# SV60mALEDs.net
KiCad netlist of a schematic drawn in EAGLE
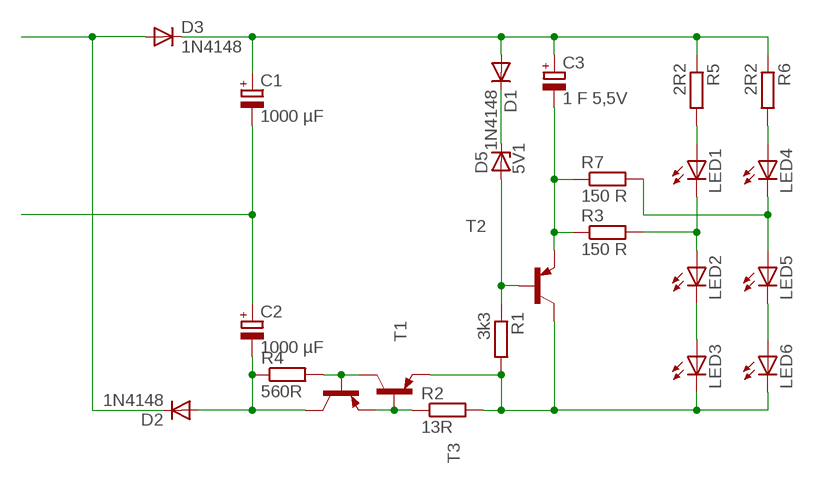
[diagram p0: schematic, sheet 1]

(export (version "E")
  (design (tool "Eeschema 10.0.6"))
  (components
    (comp (ref "C1")
      (value "1000 µF")
      (footprint "eagle-import:E5-10,5")
      (libsource (lib "eagle-import") (part "CPOL-EUE5-10.5"))
    )
    (comp (ref "C2")
      (value "1000 µF")
      (footprint "eagle-import:E5-10,5")
      (libsource (lib "eagle-import") (part "CPOL-EUE5-10.5"))
    )
    (comp (ref "C3")
      (value "1 F 5,5V")
      (footprint "eagle-import:E3,5-10")
      (libsource (lib "eagle-import") (part "CPOL-EUE3.5-10"))
    )
    (comp (ref "D1")
      (value "1N4148")
      (footprint "eagle-import:DO35-10")
      (libsource (lib "eagle-import") (part "1N4148DO35-10"))
    )
    (comp (ref "D2")
      (value "1N4148")
      (footprint "eagle-import:DO35-10")
      (libsource (lib "eagle-import") (part "1N4148DO35-10"))
    )
    (comp (ref "D3")
      (value "1N4148")
      (footprint "eagle-import:DO35-10")
      (libsource (lib "eagle-import") (part "1N4148DO35-10"))
    )
    (comp (ref "D5")
      (value "5V1")
      (footprint "eagle-import:SOD81")
      (libsource (lib "eagle-import") (part "BZD23"))
    )
    (comp (ref "LED1")
      (value "LED5MM")
      (footprint "eagle-import:LED5MM")
      (libsource (lib "eagle-import") (part "LED5MM"))
    )
    (comp (ref "LED2")
      (value "LED5MM")
      (footprint "eagle-import:LED5MM")
      (libsource (lib "eagle-import") (part "LED5MM"))
    )
    (comp (ref "LED3")
      (value "LED5MM")
      (footprint "eagle-import:LED5MM")
      (libsource (lib "eagle-import") (part "LED5MM"))
    )
    (comp (ref "LED4")
      (value "LED5MM")
      (footprint "eagle-import:LED5MM")
      (libsource (lib "eagle-import") (part "LED5MM"))
    )
    (comp (ref "LED5")
      (value "LED5MM")
      (footprint "eagle-import:LED5MM")
      (libsource (lib "eagle-import") (part "LED5MM"))
    )
    (comp (ref "LED6")
      (value "LED5MM")
      (footprint "eagle-import:LED5MM")
      (libsource (lib "eagle-import") (part "LED5MM"))
    )
    (comp (ref "R1")
      (value "3k3")
      (footprint "eagle-import:0207_10")
      (libsource (lib "eagle-import") (part "R-EU_0207/10"))
    )
    (comp (ref "R2")
      (value "13R")
      (footprint "eagle-import:0207_10")
      (libsource (lib "eagle-import") (part "R-EU_0207/10"))
    )
    (comp (ref "R3")
      (value "150 R")
      (footprint "eagle-import:0207_10")
      (libsource (lib "eagle-import") (part "R-EU_0207/10"))
    )
    (comp (ref "R4")
      (value "560R")
      (footprint "eagle-import:0207_12")
      (libsource (lib "eagle-import") (part "R-EU_0207/12"))
    )
    (comp (ref "R5")
      (value "2R2")
      (footprint "eagle-import:0207_10")
      (libsource (lib "eagle-import") (part "R-EU_0207/10"))
    )
    (comp (ref "R6")
      (value "2R2")
      (footprint "eagle-import:0207_10")
      (libsource (lib "eagle-import") (part "R-EU_0207/10"))
    )
    (comp (ref "R7")
      (value "150 R")
      (footprint "eagle-import:0207_10")
      (libsource (lib "eagle-import") (part "R-EU_0207/10"))
    )
    (comp (ref "T1")
      (value "2N2907-PNP-TO18-EBC")
      (footprint "eagle-import:TO18")
      (libsource (lib "eagle-import") (part "-PNP-TO18-EBC2N2907"))
    )
    (comp (ref "T2")
      (value "2N2907-PNP-TO18-EBC")
      (footprint "eagle-import:TO18")
      (libsource (lib "eagle-import") (part "-PNP-TO18-EBC2N2907"))
    )
    (comp (ref "T3")
      (value "2N2907-PNP-TO18-EBC")
      (footprint "eagle-import:TO18")
      (libsource (lib "eagle-import") (part "-PNP-TO18-EBC2N2907"))
    )
  )
  (nets
    (net (code "1") (name "Net-(C1-Pad+)") (class "Default")
      (node (ref "C1") (pin "+") (pinfunction "+_+") (pintype "passive"))
      (node (ref "C3") (pin "+") (pinfunction "+_+") (pintype "passive"))
      (node (ref "D1") (pin "A") (pinfunction "A_A") (pintype "passive"))
      (node (ref "D3") (pin "C") (pinfunction "C_C") (pintype "passive"))
      (node (ref "R5") (pin "1") (pinfunction "1_1") (pintype "passive"))
      (node (ref "R6") (pin "1") (pinfunction "1_1") (pintype "passive"))
    )
    (net (code "2") (name "Net-(C1-Pad-)") (class "Default")
      (node (ref "C1") (pin "-") (pinfunction "-_-") (pintype "passive"))
      (node (ref "C2") (pin "+") (pinfunction "+_+") (pintype "passive"))
    )
    (net (code "3") (name "Net-(D1-PadC)") (class "Default")
      (node (ref "D1") (pin "C") (pinfunction "C_C") (pintype "passive"))
      (node (ref "D5") (pin "C") (pinfunction "C_C") (pintype "passive"))
    )
    (net (code "4") (name "Net-(D2-PadC)") (class "Default")
      (node (ref "D2") (pin "C") (pinfunction "C_C") (pintype "passive"))
      (node (ref "D3") (pin "A") (pinfunction "A_A") (pintype "passive"))
    )
    (net (code "5") (name "Net-(LED1-C)") (class "Default")
      (node (ref "LED1") (pin "K") (pinfunction "C_K") (pintype "passive"))
      (node (ref "LED2") (pin "A") (pinfunction "A_A") (pintype "passive"))
      (node (ref "R3") (pin "2") (pinfunction "2_2") (pintype "passive"))
    )
    (net (code "6") (name "Net-(LED1-PadA)") (class "Default")
      (node (ref "LED1") (pin "A") (pinfunction "A_A") (pintype "passive"))
      (node (ref "R5") (pin "2") (pinfunction "2_2") (pintype "passive"))
    )
    (net (code "7") (name "Net-(LED2-C)") (class "Default")
      (node (ref "LED2") (pin "K") (pinfunction "C_K") (pintype "passive"))
      (node (ref "LED3") (pin "A") (pinfunction "A_A") (pintype "passive"))
    )
    (net (code "8") (name "Net-(LED3-C)") (class "Default")
      (node (ref "LED3") (pin "K") (pinfunction "C_K") (pintype "passive"))
      (node (ref "LED6") (pin "K") (pinfunction "C_K") (pintype "passive"))
      (node (ref "R1") (pin "2") (pinfunction "2_2") (pintype "passive"))
      (node (ref "R2") (pin "2") (pinfunction "2_2") (pintype "passive"))
      (node (ref "T2") (pin "3") (pinfunction "C_3") (pintype "passive"))
      (node (ref "T3") (pin "1") (pinfunction "E_1") (pintype "passive"))
    )
    (net (code "9") (name "Net-(LED4-C)") (class "Default")
      (node (ref "LED4") (pin "K") (pinfunction "C_K") (pintype "passive"))
      (node (ref "LED5") (pin "A") (pinfunction "A_A") (pintype "passive"))
      (node (ref "R7") (pin "2") (pinfunction "2_2") (pintype "passive"))
    )
    (net (code "10") (name "Net-(LED4-PadA)") (class "Default")
      (node (ref "LED4") (pin "A") (pinfunction "A_A") (pintype "passive"))
      (node (ref "R6") (pin "2") (pinfunction "2_2") (pintype "passive"))
    )
    (net (code "11") (name "Net-(LED5-C)") (class "Default")
      (node (ref "LED5") (pin "K") (pinfunction "C_K") (pintype "passive"))
      (node (ref "LED6") (pin "A") (pinfunction "A_A") (pintype "passive"))
    )
    (net (code "12") (name "Net-(T1-B)") (class "Default")
      (node (ref "R4") (pin "2") (pinfunction "2_2") (pintype "passive"))
      (node (ref "T1") (pin "2") (pinfunction "B_2") (pintype "passive"))
      (node (ref "T3") (pin "3") (pinfunction "C_3") (pintype "passive"))
    )
    (net (code "13") (name "Net-(T1-C)") (class "Default")
      (node (ref "C2") (pin "-") (pinfunction "-_-") (pintype "passive"))
      (node (ref "D2") (pin "A") (pinfunction "A_A") (pintype "passive"))
      (node (ref "R4") (pin "1") (pinfunction "1_1") (pintype "passive"))
      (node (ref "T1") (pin "3") (pinfunction "C_3") (pintype "passive"))
    )
    (net (code "14") (name "Net-(T1-E)") (class "Default")
      (node (ref "R2") (pin "1") (pinfunction "1_1") (pintype "passive"))
      (node (ref "T1") (pin "1") (pinfunction "E_1") (pintype "passive"))
      (node (ref "T3") (pin "2") (pinfunction "B_2") (pintype "passive"))
    )
    (net (code "15") (name "Net-(T2-B)") (class "Default")
      (node (ref "D5") (pin "A") (pinfunction "A_A") (pintype "passive"))
      (node (ref "R1") (pin "1") (pinfunction "1_1") (pintype "passive"))
      (node (ref "T2") (pin "2") (pinfunction "B_2") (pintype "passive"))
    )
    (net (code "16") (name "Net-(T2-E)") (class "Default")
      (node (ref "C3") (pin "-") (pinfunction "-_-") (pintype "passive"))
      (node (ref "R3") (pin "1") (pinfunction "1_1") (pintype "passive"))
      (node (ref "R7") (pin "1") (pinfunction "1_1") (pintype "passive"))
      (node (ref "T2") (pin "1") (pinfunction "E_1") (pintype "passive"))
    )
  )
)
